# my_bcd_clock.net
KiCad netlist of a schematic drawn in Altium Designer
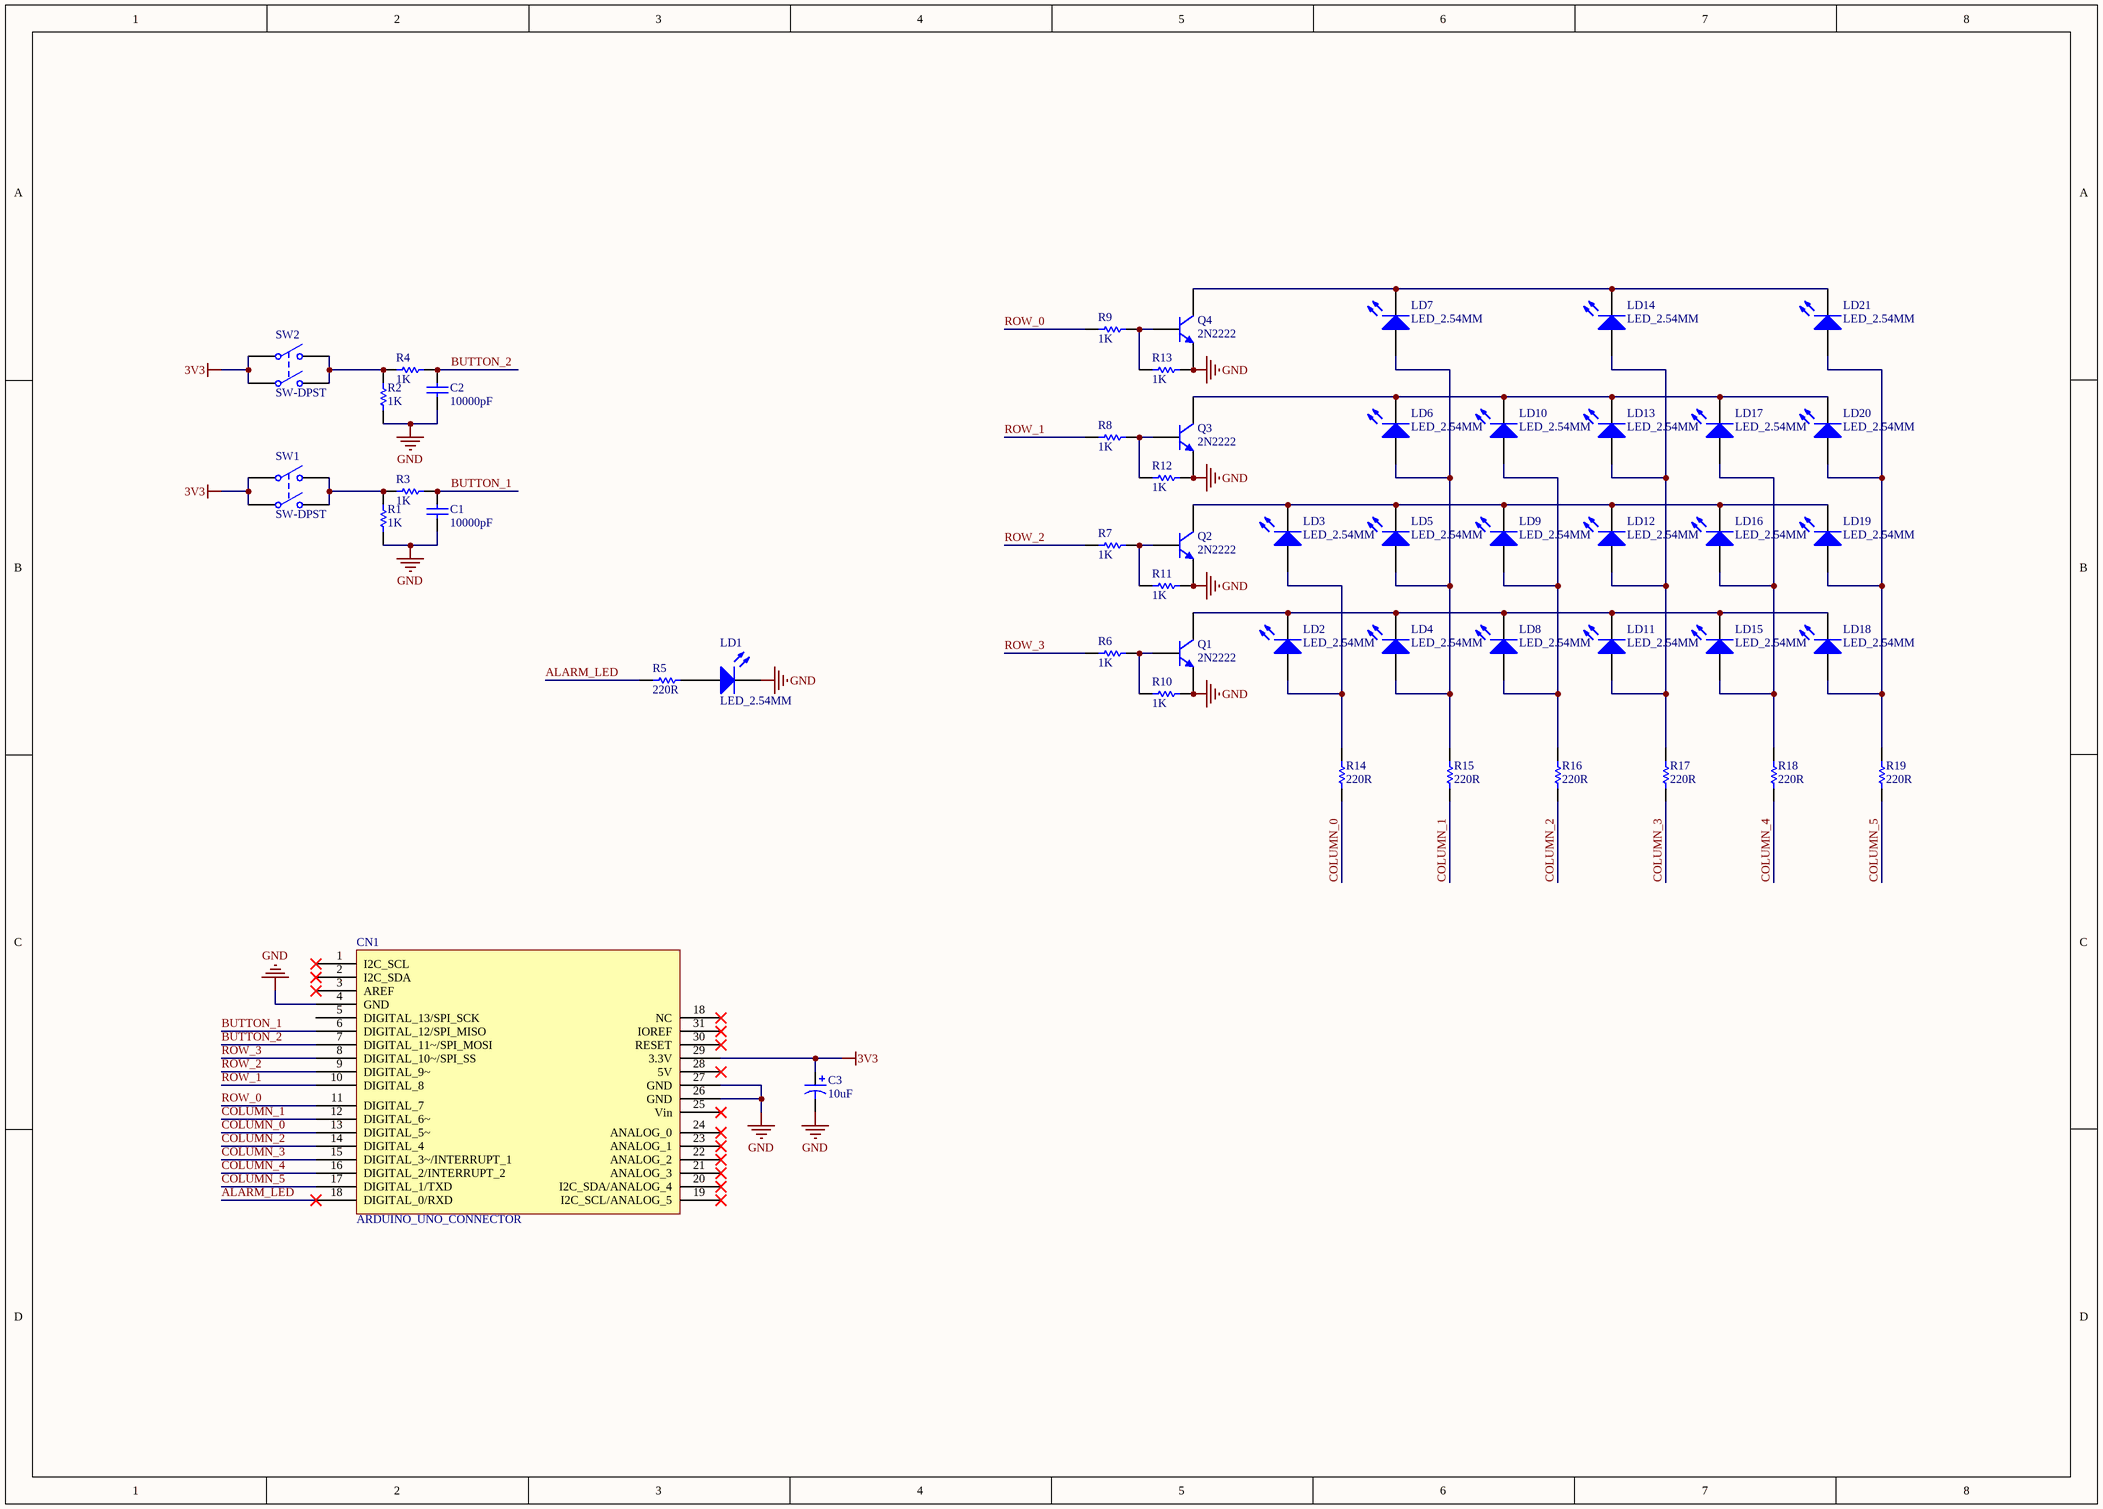
[diagram p0: my_bcd_clock.SchDoc]

(export (version "E")
  (design (tool "Eeschema 10.0.6"))
  (components
    (comp (ref "C1")
      (value "10000pF")
      (footprint "RAD-0.3")
      (description "Capacitor")
      (libsource (lib "Miscellaneous Devices") (part "Cap"))
    )
    (comp (ref "C2")
      (value "10000pF")
      (footprint "RAD-0.3")
      (description "Capacitor")
      (libsource (lib "Miscellaneous Devices") (part "Cap"))
    )
    (comp (ref "C3")
      (value "10uF")
      (footprint "RADIAL_CAN_5MM")
      (description "Capacitor")
      (libsource (lib "Miscellaneous Devices") (part "Cap Pol1"))
    )
    (comp (ref "CN1")
      (value "ARDUINO_UNO_CONNECTOR")
      (footprint "ARDUINO_UNO_CONNECTOR")
      (description "Connector")
      (libsource (lib "my_altium_library") (part "ARDUINO_UNO_CONNECTOR"))
    )
    (comp (ref "LD1")
      (value "LED_2.54MM")
      (footprint "LED_2.54MM")
      (description "LED")
      (libsource (lib "Miscellaneous Devices") (part "LED0"))
    )
    (comp (ref "LD2")
      (value "LED_2.54MM")
      (footprint "LED_2.54MM")
      (description "LED")
      (libsource (lib "Miscellaneous Devices") (part "LED0"))
    )
    (comp (ref "LD3")
      (value "LED_2.54MM")
      (footprint "LED_2.54MM")
      (description "LED")
      (libsource (lib "Miscellaneous Devices") (part "LED0"))
    )
    (comp (ref "LD4")
      (value "LED_2.54MM")
      (footprint "LED_2.54MM")
      (description "LED")
      (libsource (lib "Miscellaneous Devices") (part "LED0"))
    )
    (comp (ref "LD5")
      (value "LED_2.54MM")
      (footprint "LED_2.54MM")
      (description "LED")
      (libsource (lib "Miscellaneous Devices") (part "LED0"))
    )
    (comp (ref "LD6")
      (value "LED_2.54MM")
      (footprint "LED_2.54MM")
      (description "LED")
      (libsource (lib "Miscellaneous Devices") (part "LED0"))
    )
    (comp (ref "LD7")
      (value "LED_2.54MM")
      (footprint "LED_2.54MM")
      (description "LED")
      (libsource (lib "Miscellaneous Devices") (part "LED0"))
    )
    (comp (ref "LD8")
      (value "LED_2.54MM")
      (footprint "LED_2.54MM")
      (description "LED")
      (libsource (lib "Miscellaneous Devices") (part "LED0"))
    )
    (comp (ref "LD9")
      (value "LED_2.54MM")
      (footprint "LED_2.54MM")
      (description "LED")
      (libsource (lib "Miscellaneous Devices") (part "LED0"))
    )
    (comp (ref "LD10")
      (value "LED_2.54MM")
      (footprint "LED_2.54MM")
      (description "LED")
      (libsource (lib "Miscellaneous Devices") (part "LED0"))
    )
    (comp (ref "LD11")
      (value "LED_2.54MM")
      (footprint "LED_2.54MM")
      (description "LED")
      (libsource (lib "Miscellaneous Devices") (part "LED0"))
    )
    (comp (ref "LD12")
      (value "LED_2.54MM")
      (footprint "LED_2.54MM")
      (description "LED")
      (libsource (lib "Miscellaneous Devices") (part "LED0"))
    )
    (comp (ref "LD13")
      (value "LED_2.54MM")
      (footprint "LED_2.54MM")
      (description "LED")
      (libsource (lib "Miscellaneous Devices") (part "LED0"))
    )
    (comp (ref "LD14")
      (value "LED_2.54MM")
      (footprint "LED_2.54MM")
      (description "LED")
      (libsource (lib "Miscellaneous Devices") (part "LED0"))
    )
    (comp (ref "LD15")
      (value "LED_2.54MM")
      (footprint "LED_2.54MM")
      (description "LED")
      (libsource (lib "Miscellaneous Devices") (part "LED0"))
    )
    (comp (ref "LD16")
      (value "LED_2.54MM")
      (footprint "LED_2.54MM")
      (description "LED")
      (libsource (lib "Miscellaneous Devices") (part "LED0"))
    )
    (comp (ref "LD17")
      (value "LED_2.54MM")
      (footprint "LED_2.54MM")
      (description "LED")
      (libsource (lib "Miscellaneous Devices") (part "LED0"))
    )
    (comp (ref "LD18")
      (value "LED_2.54MM")
      (footprint "LED_2.54MM")
      (description "LED")
      (libsource (lib "Miscellaneous Devices") (part "LED0"))
    )
    (comp (ref "LD19")
      (value "LED_2.54MM")
      (footprint "LED_2.54MM")
      (description "LED")
      (libsource (lib "Miscellaneous Devices") (part "LED0"))
    )
    (comp (ref "LD20")
      (value "LED_2.54MM")
      (footprint "LED_2.54MM")
      (description "LED")
      (libsource (lib "Miscellaneous Devices") (part "LED0"))
    )
    (comp (ref "LD21")
      (value "LED_2.54MM")
      (footprint "LED_2.54MM")
      (description "LED")
      (libsource (lib "Miscellaneous Devices") (part "LED0"))
    )
    (comp (ref "Q1")
      (value "2N2222")
      (footprint "TO-226-AA")
      (description "NPN")
      (libsource (lib "Miscellaneous Devices") (part "NPN"))
    )
    (comp (ref "Q2")
      (value "2N2222")
      (footprint "TO-226-AA")
      (description "NPN")
      (libsource (lib "Miscellaneous Devices") (part "NPN"))
    )
    (comp (ref "Q3")
      (value "2N2222")
      (footprint "TO-226-AA")
      (description "NPN")
      (libsource (lib "Miscellaneous Devices") (part "NPN"))
    )
    (comp (ref "Q4")
      (value "2N2222")
      (footprint "TO-226-AA")
      (description "NPN")
      (libsource (lib "Miscellaneous Devices") (part "NPN"))
    )
    (comp (ref "R1")
      (value "1K")
      (footprint "AXIAL-0.3")
      (description "Resistor")
      (libsource (lib "Miscellaneous Devices") (part "Res1"))
    )
    (comp (ref "R2")
      (value "1K")
      (footprint "AXIAL-0.3")
      (description "Resistor")
      (libsource (lib "Miscellaneous Devices") (part "Res1"))
    )
    (comp (ref "R3")
      (value "1K")
      (footprint "AXIAL-0.3")
      (description "Resistor")
      (libsource (lib "Miscellaneous Devices") (part "Res1"))
    )
    (comp (ref "R4")
      (value "1K")
      (footprint "AXIAL-0.3")
      (description "Resistor")
      (libsource (lib "Miscellaneous Devices") (part "Res1"))
    )
    (comp (ref "R5")
      (value "220R")
      (footprint "AXIAL-0.3")
      (description "Resistor")
      (libsource (lib "Miscellaneous Devices") (part "Res1"))
    )
    (comp (ref "R6")
      (value "1K")
      (footprint "AXIAL-0.3")
      (description "Resistor")
      (libsource (lib "Miscellaneous Devices") (part "Res1"))
    )
    (comp (ref "R7")
      (value "1K")
      (footprint "AXIAL-0.3")
      (description "Resistor")
      (libsource (lib "Miscellaneous Devices") (part "Res1"))
    )
    (comp (ref "R8")
      (value "1K")
      (footprint "AXIAL-0.3")
      (description "Resistor")
      (libsource (lib "Miscellaneous Devices") (part "Res1"))
    )
    (comp (ref "R9")
      (value "1K")
      (footprint "AXIAL-0.3")
      (description "Resistor")
      (libsource (lib "Miscellaneous Devices") (part "Res1"))
    )
    (comp (ref "R10")
      (value "1K")
      (footprint "AXIAL-0.3")
      (description "Resistor")
      (libsource (lib "Miscellaneous Devices") (part "Res1"))
    )
    (comp (ref "R11")
      (value "1K")
      (footprint "AXIAL-0.3")
      (description "Resistor")
      (libsource (lib "Miscellaneous Devices") (part "Res1"))
    )
    (comp (ref "R12")
      (value "1K")
      (footprint "AXIAL-0.3")
      (description "Resistor")
      (libsource (lib "Miscellaneous Devices") (part "Res1"))
    )
    (comp (ref "R13")
      (value "1K")
      (footprint "AXIAL-0.3")
      (description "Resistor")
      (libsource (lib "Miscellaneous Devices") (part "Res1"))
    )
    (comp (ref "R14")
      (value "220R")
      (footprint "AXIAL-0.3")
      (description "Resistor")
      (libsource (lib "Miscellaneous Devices") (part "Res1"))
    )
    (comp (ref "R15")
      (value "220R")
      (footprint "AXIAL-0.3")
      (description "Resistor")
      (libsource (lib "Miscellaneous Devices") (part "Res1"))
    )
    (comp (ref "R16")
      (value "220R")
      (footprint "AXIAL-0.3")
      (description "Resistor")
      (libsource (lib "Miscellaneous Devices") (part "Res1"))
    )
    (comp (ref "R17")
      (value "220R")
      (footprint "AXIAL-0.3")
      (description "Resistor")
      (libsource (lib "Miscellaneous Devices") (part "Res1"))
    )
    (comp (ref "R18")
      (value "220R")
      (footprint "AXIAL-0.3")
      (description "Resistor")
      (libsource (lib "Miscellaneous Devices") (part "Res1"))
    )
    (comp (ref "R19")
      (value "220R")
      (footprint "AXIAL-0.3")
      (description "Resistor")
      (libsource (lib "Miscellaneous Devices") (part "Res1"))
    )
    (comp (ref "SW1")
      (value "SW-DPST")
      (footprint "DPST-4")
      (description "Switch")
      (libsource (lib "Miscellaneous Devices") (part "SW-DPST"))
    )
    (comp (ref "SW2")
      (value "SW-DPST")
      (footprint "DPST-4")
      (description "Switch")
      (libsource (lib "Miscellaneous Devices") (part "SW-DPST"))
    )
  )
  (nets
    (net (code "1") (name "/ALARM_LED") (class "Default")
      (node (ref "CN1") (pin "18") (pinfunction "DIGITAL_0/RXD_18") (pintype "passive"))
      (node (ref "R5") (pin "2") (pinfunction "2_2") (pintype "passive"))
    )
    (net (code "2") (name "/BUTTON_1") (class "Default")
      (node (ref "C1") (pin "1") (pinfunction "1_1") (pintype "passive"))
      (node (ref "CN1") (pin "6") (pinfunction "DIGITAL_12/SPI_MISO_6") (pintype "passive"))
      (node (ref "R3") (pin "2") (pinfunction "2_2") (pintype "passive"))
    )
    (net (code "3") (name "/BUTTON_2") (class "Default")
      (node (ref "C2") (pin "1") (pinfunction "1_1") (pintype "passive"))
      (node (ref "CN1") (pin "7") (pinfunction "DIGITAL_11~/SPI_MOSI_7") (pintype "passive"))
      (node (ref "R4") (pin "2") (pinfunction "2_2") (pintype "passive"))
    )
    (net (code "4") (name "/COLUMN_0") (class "Default")
      (node (ref "CN1") (pin "13") (pinfunction "DIGITAL_5~_13") (pintype "passive"))
      (node (ref "R14") (pin "1") (pinfunction "1_1") (pintype "passive"))
    )
    (net (code "5") (name "/COLUMN_1") (class "Default")
      (node (ref "CN1") (pin "12") (pinfunction "DIGITAL_6~_12") (pintype "passive"))
      (node (ref "R15") (pin "1") (pinfunction "1_1") (pintype "passive"))
    )
    (net (code "6") (name "/COLUMN_2") (class "Default")
      (node (ref "CN1") (pin "14") (pinfunction "DIGITAL_4_14") (pintype "passive"))
      (node (ref "R16") (pin "1") (pinfunction "1_1") (pintype "passive"))
    )
    (net (code "7") (name "/COLUMN_3") (class "Default")
      (node (ref "CN1") (pin "15") (pinfunction "DIGITAL_3~/INTERRUPT_1_15") (pintype "passive"))
      (node (ref "R17") (pin "1") (pinfunction "1_1") (pintype "passive"))
    )
    (net (code "8") (name "/COLUMN_4") (class "Default")
      (node (ref "CN1") (pin "16") (pinfunction "DIGITAL_2/INTERRUPT_2_16") (pintype "passive"))
      (node (ref "R18") (pin "1") (pinfunction "1_1") (pintype "passive"))
    )
    (net (code "9") (name "/COLUMN_5") (class "Default")
      (node (ref "CN1") (pin "17") (pinfunction "DIGITAL_1/TXD_17") (pintype "passive"))
      (node (ref "R19") (pin "1") (pinfunction "1_1") (pintype "passive"))
    )
    (net (code "10") (name "/ROW_0") (class "Default")
      (node (ref "CN1") (pin "11") (pinfunction "DIGITAL_7_11") (pintype "passive"))
      (node (ref "R9") (pin "1") (pinfunction "1_1") (pintype "passive"))
    )
    (net (code "11") (name "/ROW_1") (class "Default")
      (node (ref "CN1") (pin "10") (pinfunction "DIGITAL_8_10") (pintype "passive"))
      (node (ref "R8") (pin "1") (pinfunction "1_1") (pintype "passive"))
    )
    (net (code "12") (name "/ROW_2") (class "Default")
      (node (ref "CN1") (pin "9") (pinfunction "DIGITAL_9~_9") (pintype "passive"))
      (node (ref "R7") (pin "1") (pinfunction "1_1") (pintype "passive"))
    )
    (net (code "13") (name "/ROW_3") (class "Default")
      (node (ref "CN1") (pin "8") (pinfunction "DIGITAL_10~/SPI_SS_8") (pintype "passive"))
      (node (ref "R6") (pin "2") (pinfunction "2_2") (pintype "passive"))
    )
    (net (code "14") (name "3V3") (class "Default")
      (node (ref "C3") (pin "1") (pinfunction "1_1") (pintype "passive"))
      (node (ref "CN1") (pin "29") (pinfunction "3.3V_29") (pintype "passive"))
      (node (ref "SW1") (pin "1") (pinfunction "COMMON1_1") (pintype "passive"))
      (node (ref "SW1") (pin "3") (pinfunction "COMMON2_3") (pintype "passive"))
      (node (ref "SW2") (pin "1") (pinfunction "COMMON1_1") (pintype "passive"))
      (node (ref "SW2") (pin "3") (pinfunction "COMMON2_3") (pintype "passive"))
    )
    (net (code "15") (name "GND") (class "Default")
      (node (ref "C1") (pin "2") (pinfunction "2_2") (pintype "passive"))
      (node (ref "C2") (pin "2") (pinfunction "2_2") (pintype "passive"))
      (node (ref "C3") (pin "2") (pinfunction "2_2") (pintype "passive"))
      (node (ref "CN1") (pin "26") (pinfunction "GND_26") (pintype "passive"))
      (node (ref "CN1") (pin "27") (pinfunction "GND_27") (pintype "passive"))
      (node (ref "CN1") (pin "4") (pinfunction "GND_4") (pintype "passive"))
      (node (ref "LD1") (pin "2") (pinfunction "K_2") (pintype "passive"))
      (node (ref "Q1") (pin "3") (pinfunction "E_3") (pintype "passive"))
      (node (ref "Q2") (pin "3") (pinfunction "E_3") (pintype "passive"))
      (node (ref "Q3") (pin "3") (pinfunction "E_3") (pintype "passive"))
      (node (ref "Q4") (pin "3") (pinfunction "E_3") (pintype "passive"))
      (node (ref "R1") (pin "1") (pinfunction "1_1") (pintype "passive"))
      (node (ref "R10") (pin "1") (pinfunction "1_1") (pintype "passive"))
      (node (ref "R11") (pin "1") (pinfunction "1_1") (pintype "passive"))
      (node (ref "R12") (pin "1") (pinfunction "1_1") (pintype "passive"))
      (node (ref "R13") (pin "2") (pinfunction "2_2") (pintype "passive"))
      (node (ref "R2") (pin "1") (pinfunction "1_1") (pintype "passive"))
    )
    (net (code "16") (name "Net-(LD1-A)") (class "Default")
      (node (ref "LD1") (pin "1") (pinfunction "A_1") (pintype "passive"))
      (node (ref "R5") (pin "1") (pinfunction "1_1") (pintype "passive"))
    )
    (net (code "17") (name "Net-(LD2-A)") (class "Default")
      (node (ref "LD2") (pin "1") (pinfunction "A_1") (pintype "passive"))
      (node (ref "LD3") (pin "1") (pinfunction "A_1") (pintype "passive"))
      (node (ref "R14") (pin "2") (pinfunction "2_2") (pintype "passive"))
    )
    (net (code "18") (name "Net-(LD4-A)") (class "Default")
      (node (ref "LD4") (pin "1") (pinfunction "A_1") (pintype "passive"))
      (node (ref "LD5") (pin "1") (pinfunction "A_1") (pintype "passive"))
      (node (ref "LD6") (pin "1") (pinfunction "A_1") (pintype "passive"))
      (node (ref "LD7") (pin "1") (pinfunction "A_1") (pintype "passive"))
      (node (ref "R15") (pin "2") (pinfunction "2_2") (pintype "passive"))
    )
    (net (code "19") (name "Net-(LD10-A)") (class "Default")
      (node (ref "LD10") (pin "1") (pinfunction "A_1") (pintype "passive"))
      (node (ref "LD8") (pin "1") (pinfunction "A_1") (pintype "passive"))
      (node (ref "LD9") (pin "1") (pinfunction "A_1") (pintype "passive"))
      (node (ref "R16") (pin "2") (pinfunction "2_2") (pintype "passive"))
    )
    (net (code "20") (name "Net-(LD10-K)") (class "Default")
      (node (ref "LD10") (pin "2") (pinfunction "K_2") (pintype "passive"))
      (node (ref "LD13") (pin "2") (pinfunction "K_2") (pintype "passive"))
      (node (ref "LD17") (pin "2") (pinfunction "K_2") (pintype "passive"))
      (node (ref "LD20") (pin "2") (pinfunction "K_2") (pintype "passive"))
      (node (ref "LD6") (pin "2") (pinfunction "K_2") (pintype "passive"))
      (node (ref "Q3") (pin "1") (pinfunction "C_1") (pintype "passive"))
    )
    (net (code "21") (name "Net-(LD11-A)") (class "Default")
      (node (ref "LD11") (pin "1") (pinfunction "A_1") (pintype "passive"))
      (node (ref "LD12") (pin "1") (pinfunction "A_1") (pintype "passive"))
      (node (ref "LD13") (pin "1") (pinfunction "A_1") (pintype "passive"))
      (node (ref "LD14") (pin "1") (pinfunction "A_1") (pintype "passive"))
      (node (ref "R17") (pin "2") (pinfunction "2_2") (pintype "passive"))
    )
    (net (code "22") (name "Net-(LD11-K)") (class "Default")
      (node (ref "LD11") (pin "2") (pinfunction "K_2") (pintype "passive"))
      (node (ref "LD15") (pin "2") (pinfunction "K_2") (pintype "passive"))
      (node (ref "LD18") (pin "2") (pinfunction "K_2") (pintype "passive"))
      (node (ref "LD2") (pin "2") (pinfunction "K_2") (pintype "passive"))
      (node (ref "LD4") (pin "2") (pinfunction "K_2") (pintype "passive"))
      (node (ref "LD8") (pin "2") (pinfunction "K_2") (pintype "passive"))
      (node (ref "Q1") (pin "1") (pinfunction "C_1") (pintype "passive"))
    )
    (net (code "23") (name "Net-(LD12-K)") (class "Default")
      (node (ref "LD12") (pin "2") (pinfunction "K_2") (pintype "passive"))
      (node (ref "LD16") (pin "2") (pinfunction "K_2") (pintype "passive"))
      (node (ref "LD19") (pin "2") (pinfunction "K_2") (pintype "passive"))
      (node (ref "LD3") (pin "2") (pinfunction "K_2") (pintype "passive"))
      (node (ref "LD5") (pin "2") (pinfunction "K_2") (pintype "passive"))
      (node (ref "LD9") (pin "2") (pinfunction "K_2") (pintype "passive"))
      (node (ref "Q2") (pin "1") (pinfunction "C_1") (pintype "passive"))
    )
    (net (code "24") (name "Net-(LD14-K)") (class "Default")
      (node (ref "LD14") (pin "2") (pinfunction "K_2") (pintype "passive"))
      (node (ref "LD21") (pin "2") (pinfunction "K_2") (pintype "passive"))
      (node (ref "LD7") (pin "2") (pinfunction "K_2") (pintype "passive"))
      (node (ref "Q4") (pin "1") (pinfunction "C_1") (pintype "passive"))
    )
    (net (code "25") (name "Net-(LD15-A)") (class "Default")
      (node (ref "LD15") (pin "1") (pinfunction "A_1") (pintype "passive"))
      (node (ref "LD16") (pin "1") (pinfunction "A_1") (pintype "passive"))
      (node (ref "LD17") (pin "1") (pinfunction "A_1") (pintype "passive"))
      (node (ref "R18") (pin "2") (pinfunction "2_2") (pintype "passive"))
    )
    (net (code "26") (name "Net-(LD18-A)") (class "Default")
      (node (ref "LD18") (pin "1") (pinfunction "A_1") (pintype "passive"))
      (node (ref "LD19") (pin "1") (pinfunction "A_1") (pintype "passive"))
      (node (ref "LD20") (pin "1") (pinfunction "A_1") (pintype "passive"))
      (node (ref "LD21") (pin "1") (pinfunction "A_1") (pintype "passive"))
      (node (ref "R19") (pin "2") (pinfunction "2_2") (pintype "passive"))
    )
    (net (code "27") (name "Net-(Q1-B)") (class "Default")
      (node (ref "Q1") (pin "2") (pinfunction "B_2") (pintype "passive"))
      (node (ref "R10") (pin "2") (pinfunction "2_2") (pintype "passive"))
      (node (ref "R6") (pin "1") (pinfunction "1_1") (pintype "passive"))
    )
    (net (code "28") (name "Net-(Q2-B)") (class "Default")
      (node (ref "Q2") (pin "2") (pinfunction "B_2") (pintype "passive"))
      (node (ref "R11") (pin "2") (pinfunction "2_2") (pintype "passive"))
      (node (ref "R7") (pin "2") (pinfunction "2_2") (pintype "passive"))
    )
    (net (code "29") (name "Net-(Q3-B)") (class "Default")
      (node (ref "Q3") (pin "2") (pinfunction "B_2") (pintype "passive"))
      (node (ref "R12") (pin "2") (pinfunction "2_2") (pintype "passive"))
      (node (ref "R8") (pin "2") (pinfunction "2_2") (pintype "passive"))
    )
    (net (code "30") (name "Net-(Q4-B)") (class "Default")
      (node (ref "Q4") (pin "2") (pinfunction "B_2") (pintype "passive"))
      (node (ref "R13") (pin "1") (pinfunction "1_1") (pintype "passive"))
      (node (ref "R9") (pin "2") (pinfunction "2_2") (pintype "passive"))
    )
    (net (code "31") (name "Net-(SW1-NO1)") (class "Default")
      (node (ref "R1") (pin "2") (pinfunction "2_2") (pintype "passive"))
      (node (ref "R3") (pin "1") (pinfunction "1_1") (pintype "passive"))
      (node (ref "SW1") (pin "2") (pinfunction "NO1_2") (pintype "passive"))
      (node (ref "SW1") (pin "4") (pinfunction "NO2_4") (pintype "passive"))
    )
    (net (code "32") (name "Net-(SW2-NO1)") (class "Default")
      (node (ref "R2") (pin "2") (pinfunction "2_2") (pintype "passive"))
      (node (ref "R4") (pin "1") (pinfunction "1_1") (pintype "passive"))
      (node (ref "SW2") (pin "2") (pinfunction "NO1_2") (pintype "passive"))
      (node (ref "SW2") (pin "4") (pinfunction "NO2_4") (pintype "passive"))
    )
    (net (code "33") (name "unconnected-(CN1-5V-Pad28)") (class "Default")
      (node (ref "CN1") (pin "28") (pinfunction "5V_28") (pintype "passive+no_connect"))
    )
    (net (code "34") (name "unconnected-(CN1-ANALOG_0-Pad24)") (class "Default")
      (node (ref "CN1") (pin "24") (pinfunction "ANALOG_0_24") (pintype "passive+no_connect"))
    )
    (net (code "35") (name "unconnected-(CN1-ANALOG_1-Pad23)") (class "Default")
      (node (ref "CN1") (pin "23") (pinfunction "ANALOG_1_23") (pintype "passive+no_connect"))
    )
    (net (code "36") (name "unconnected-(CN1-ANALOG_2-Pad22)") (class "Default")
      (node (ref "CN1") (pin "22") (pinfunction "ANALOG_2_22") (pintype "passive+no_connect"))
    )
    (net (code "37") (name "unconnected-(CN1-ANALOG_3-Pad21)") (class "Default")
      (node (ref "CN1") (pin "21") (pinfunction "ANALOG_3_21") (pintype "passive+no_connect"))
    )
    (net (code "38") (name "unconnected-(CN1-AREF-Pad3)") (class "Default")
      (node (ref "CN1") (pin "3") (pinfunction "AREF_3") (pintype "passive+no_connect"))
    )
    (net (code "39") (name "unconnected-(CN1-DIGITAL_13{slash}SPI_SCK-Pad5)") (class "Default")
      (node (ref "CN1") (pin "5") (pinfunction "DIGITAL_13/SPI_SCK_5") (pintype "passive"))
    )
    (net (code "40") (name "unconnected-(CN1-I2C_SCL-Pad1)") (class "Default")
      (node (ref "CN1") (pin "1") (pinfunction "I2C_SCL_1") (pintype "passive+no_connect"))
    )
    (net (code "41") (name "unconnected-(CN1-I2C_SCL{slash}ANALOG_5-Pad19)") (class "Default")
      (node (ref "CN1") (pin "19") (pinfunction "I2C_SCL/ANALOG_5_19") (pintype "passive+no_connect"))
    )
    (net (code "42") (name "unconnected-(CN1-I2C_SDA-Pad2)") (class "Default")
      (node (ref "CN1") (pin "2") (pinfunction "I2C_SDA_2") (pintype "passive+no_connect"))
    )
    (net (code "43") (name "unconnected-(CN1-I2C_SDA{slash}ANALOG_4-Pad20)") (class "Default")
      (node (ref "CN1") (pin "20") (pinfunction "I2C_SDA/ANALOG_4_20") (pintype "passive+no_connect"))
    )
    (net (code "44") (name "unconnected-(CN1-IOREF-Pad31)") (class "Default")
      (node (ref "CN1") (pin "31") (pinfunction "IOREF_31") (pintype "passive+no_connect"))
    )
    (net (code "45") (name "unconnected-(CN1-NC-Pad18)") (class "Default")
      (node (ref "CN1") (pin "18") (pinfunction "NC_18") (pintype "passive+no_connect"))
    )
    (net (code "46") (name "unconnected-(CN1-RESET-Pad30)") (class "Default")
      (node (ref "CN1") (pin "30") (pinfunction "RESET_30") (pintype "passive+no_connect"))
    )
    (net (code "47") (name "unconnected-(CN1-Vin-Pad25)") (class "Default")
      (node (ref "CN1") (pin "25") (pinfunction "Vin_25") (pintype "passive+no_connect"))
    )
  )
)
